# Safety_2019_V_3_0_BRAKE_LIGHT.net
KiCad netlist of a schematic drawn in Altium Designer
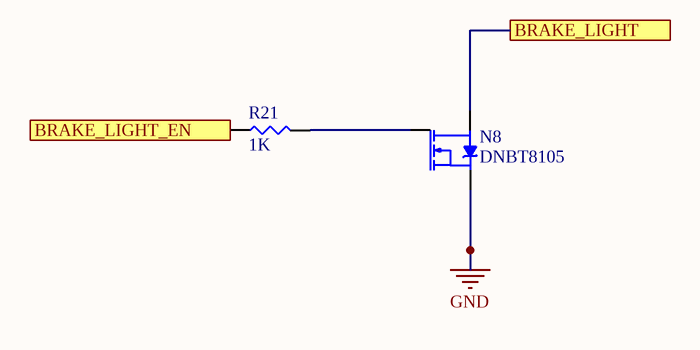
[diagram p0: Safety_2019_V_3_0_BRAKE_LIGHT.SchDoc]

(export (version "E")
  (design (tool "Eeschema 10.0.6"))
  (components
    (comp (ref "N8")
      (value "DNBT8105")
      (footprint "SOT23")
      (libsource (lib "ife19_Elec_Library") (part "NMOS-SOT23"))
    )
    (comp (ref "R21")
      (value "1K")
      (footprint "RES-0603")
      (libsource (lib "ife19_Elec_Library") (part "RES-0603"))
    )
  )
  (nets
    (net (code "1") (name "/BRAKE_LIGHT") (class "Default")
      (node (ref "N8") (pin "2") (pinfunction "S_2") (pintype "passive"))
    )
    (net (code "2") (name "/BRAKE_LIGHT_EN") (class "Default")
      (node (ref "R21") (pin "1") (pinfunction "1_1") (pintype "passive"))
    )
    (net (code "3") (name "GND") (class "Default")
      (node (ref "N8") (pin "3") (pinfunction "D_3") (pintype "passive"))
    )
    (net (code "4") (name "Net-(N8-G)") (class "Default")
      (node (ref "N8") (pin "1") (pinfunction "G_1") (pintype "passive"))
      (node (ref "R21") (pin "2") (pinfunction "2_2") (pintype "passive"))
    )
  )
)
